# ultra-violet-tooth-sensor-mk-2_3.net
KiCad netlist of a schematic drawn in EAGLE
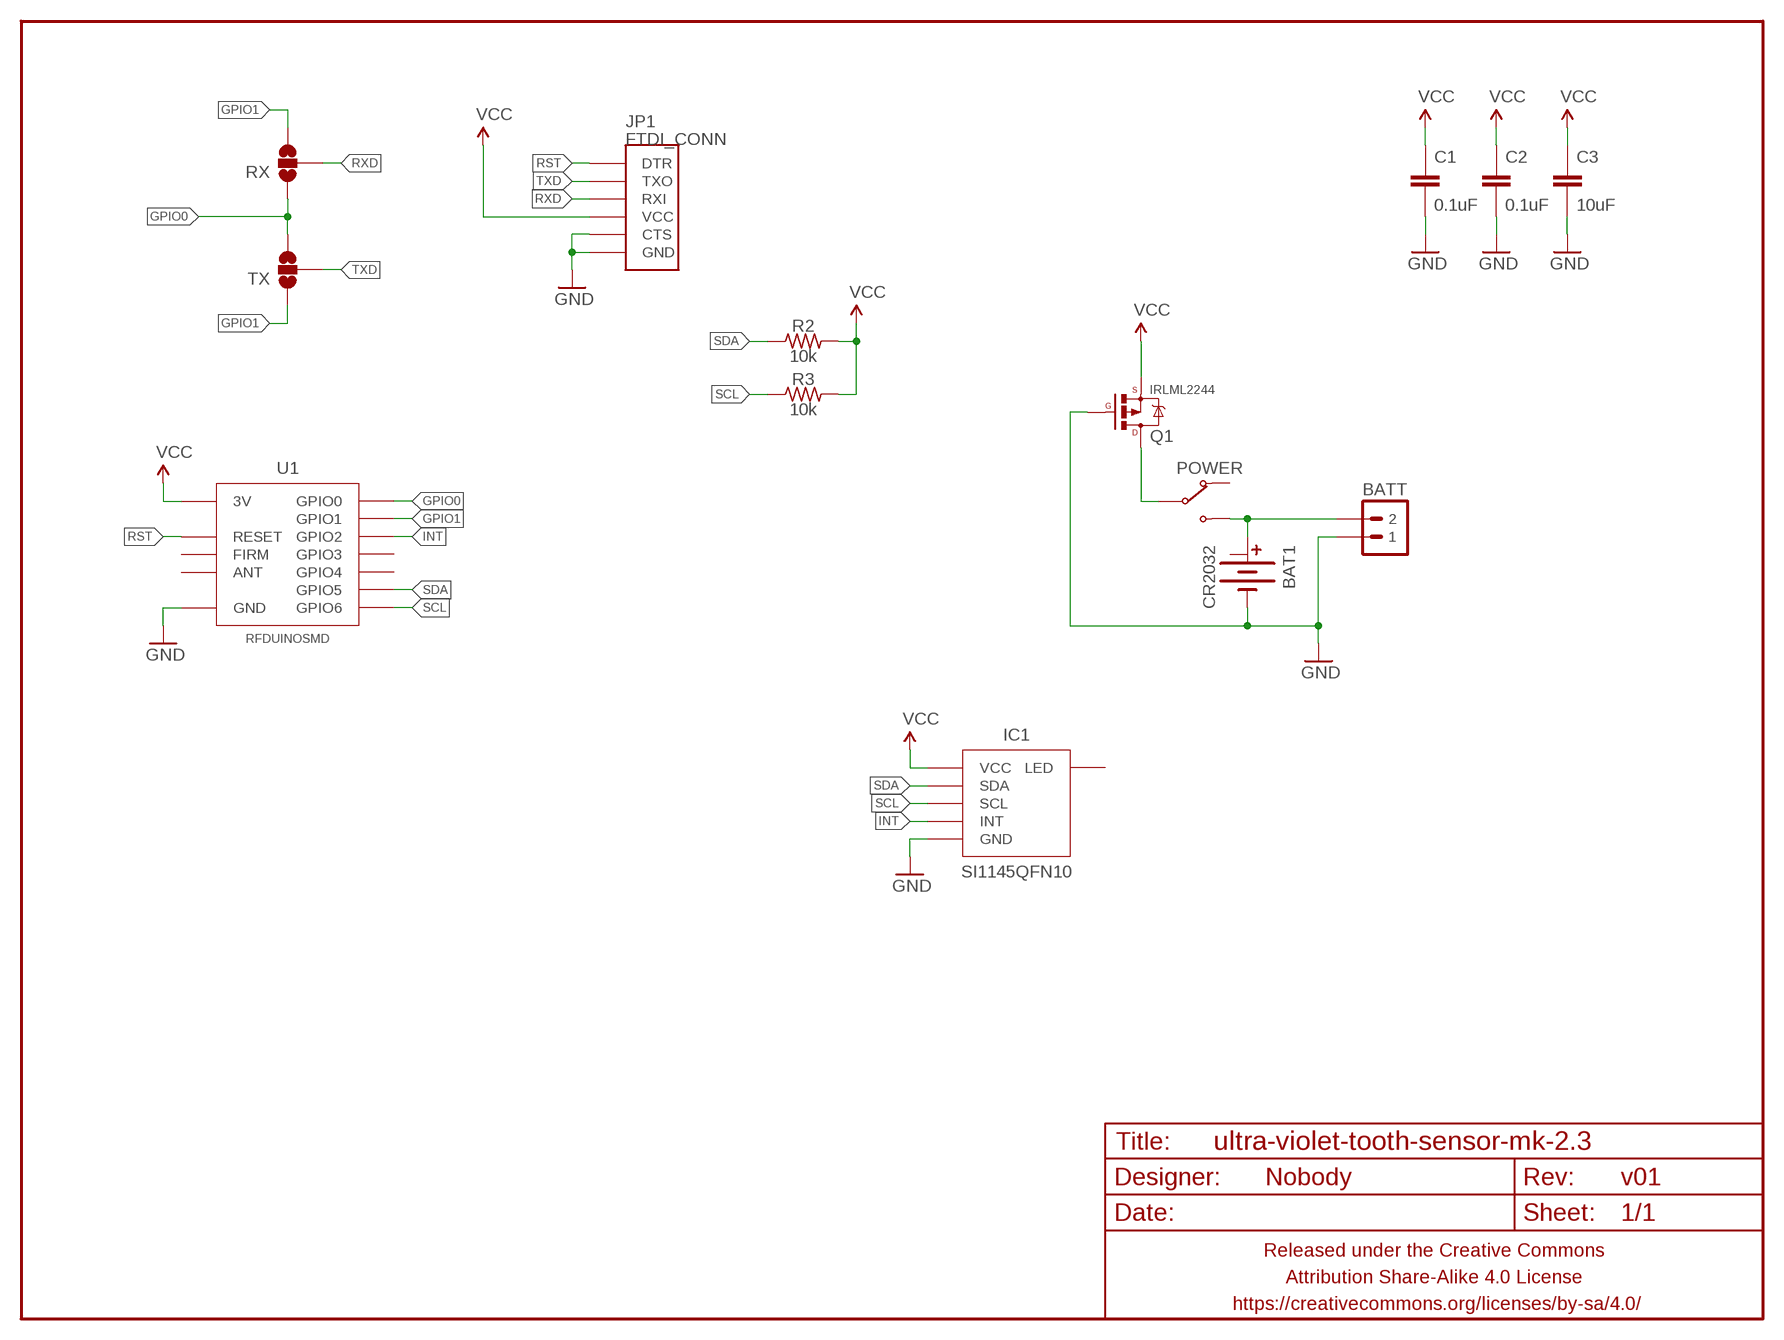
[diagram p0: schematic, sheet 1]

(export (version "E")
  (design (tool "Eeschema 10.0.6"))
  (components
    (comp (ref "BAT1")
      (value "CR2032")
      (footprint "eagle-import:BATTCON_20MM_MINE_STAHPIT")
      (libsource (lib "eagle-import") (part "BATTERY-COINCR2032_SMD_TIGHT"))
    )
    (comp (ref "BATT")
      (value "M02PTH-CENTERED-R+")
      (footprint "eagle-import:1X02-CENTER-R+")
      (libsource (lib "eagle-import") (part "M02PTH-CENTERED-R+"))
    )
    (comp (ref "C1")
      (value "0.1uF")
      (footprint "eagle-import:C0805")
      (libsource (lib "eagle-import") (part "CAPACITOR-CERAMICC0805"))
    )
    (comp (ref "C2")
      (value "0.1uF")
      (footprint "eagle-import:C0603")
      (libsource (lib "eagle-import") (part "CAPACITOR-CERAMICC0603"))
    )
    (comp (ref "C3")
      (value "10uF")
      (footprint "eagle-import:C1206")
      (libsource (lib "eagle-import") (part "CAPACITOR-CERAMICC1206"))
    )
    (comp (ref "FRAME1")
      (value "FRAME-LETTERNO_PACKAGE")
      (footprint "eagle-import:DUMMY")
      (fields (field (name "DESIGNER") "Nobody"))
      (libsource (lib "eagle-import") (part "FRAME-LETTERNO_PACKAGE"))
    )
    (comp (ref "IC1")
      (value "SI1145QFN10")
      (footprint "eagle-import:SI1145")
      (libsource (lib "eagle-import") (part "SI1145QFN10"))
    )
    (comp (ref "JP1")
      (value "FTDI_CONN")
      (footprint "eagle-import:FTDI_CONN")
      (libsource (lib "eagle-import") (part "FTDI_CONN"))
    )
    (comp (ref "POWER")
      (value "SWITCH-SPDTPCM12SMTR")
      (footprint "eagle-import:SWITCH-SPDT-SMD-RA-PCM12SMTR")
      (libsource (lib "eagle-import") (part "SWITCH-SPDTPCM12SMTR"))
    )
    (comp (ref "Q1")
      (value "IRLML2244")
      (footprint "eagle-import:SOT23-3")
      (libsource (lib "eagle-import") (part "MOSFET-PCHANNELIRLML2244"))
    )
    (comp (ref "R2")
      (value "10k")
      (footprint "eagle-import:R0603")
      (libsource (lib "eagle-import") (part "RESISTORR0603"))
    )
    (comp (ref "R3")
      (value "10k")
      (footprint "eagle-import:R0603")
      (libsource (lib "eagle-import") (part "RESISTORR0603"))
    )
    (comp (ref "RX")
      (value "JUMPER-PAD-3-NOFULL_BOX_SILK")
      (footprint "eagle-import:PAD-JUMPER-3-NO_YES_SILK_FULL_BOX")
      (libsource (lib "eagle-import") (part "JUMPER-PAD-3-NOFULL_BOX_SILK"))
    )
    (comp (ref "TX")
      (value "JUMPER-PAD-3-NOFULL_BOX_SILK")
      (footprint "eagle-import:PAD-JUMPER-3-NO_YES_SILK_FULL_BOX")
      (libsource (lib "eagle-import") (part "JUMPER-PAD-3-NOFULL_BOX_SILK"))
    )
    (comp (ref "U1")
      (value "RFDUINOSMD")
      (footprint "eagle-import:RFDUINO-SMD")
      (libsource (lib "eagle-import") (part "RFDUINOSMD"))
    )
  )
  (nets
    (net (code "1") (name "GND") (class "Default")
      (node (ref "BAT1") (pin "BOTTOM") (pinfunction "-_BOTTOM") (pintype "bidirectional"))
      (node (ref "BATT") (pin "1") (pinfunction "1_1") (pintype "passive"))
      (node (ref "C1") (pin "2") (pinfunction "2_2") (pintype "passive"))
      (node (ref "C2") (pin "2") (pinfunction "2_2") (pintype "passive"))
      (node (ref "C3") (pin "2") (pinfunction "2_2") (pintype "passive"))
      (node (ref "IC1") (pin "GND") (pinfunction "GND_GND") (pintype "bidirectional"))
      (node (ref "JP1") (pin "CTS") (pinfunction "CTS_CTS") (pintype "bidirectional"))
      (node (ref "JP1") (pin "GND") (pinfunction "GND_GND") (pintype "bidirectional"))
      (node (ref "Q1") (pin "1") (pinfunction "G_1") (pintype "passive"))
      (node (ref "U1") (pin "GND@1") (pinfunction "GND_GND@1") (pintype "bidirectional"))
      (node (ref "U1") (pin "GND@2") (pinfunction "GND_GND@2") (pintype "bidirectional"))
      (node (ref "U1") (pin "GND@3") (pinfunction "GND_GND@3") (pintype "bidirectional"))
      (node (ref "U1") (pin "GND@4") (pinfunction "GND_GND@4") (pintype "bidirectional"))
      (node (ref "U1") (pin "GND@5") (pinfunction "GND_GND@5") (pintype "bidirectional"))
      (node (ref "U1") (pin "GND@6") (pinfunction "GND_GND@6") (pintype "bidirectional"))
      (node (ref "U1") (pin "GND@7") (pinfunction "GND_GND@7") (pintype "bidirectional"))
      (node (ref "U1") (pin "GND@8") (pinfunction "GND_GND@8") (pintype "bidirectional"))
    )
    (net (code "2") (name "GPIO0") (class "Default")
      (node (ref "RX") (pin "1") (pinfunction "1_1") (pintype "passive"))
      (node (ref "TX") (pin "3") (pinfunction "3_3") (pintype "passive"))
      (node (ref "U1") (pin "GPIO0") (pinfunction "GPIO0_GPIO0") (pintype "bidirectional"))
    )
    (net (code "3") (name "GPIO1") (class "Default")
      (node (ref "RX") (pin "3") (pinfunction "3_3") (pintype "passive"))
      (node (ref "TX") (pin "1") (pinfunction "1_1") (pintype "passive"))
      (node (ref "U1") (pin "GPIO1") (pinfunction "GPIO1_GPIO1") (pintype "bidirectional"))
    )
    (net (code "4") (name "INT") (class "Default")
      (node (ref "IC1") (pin "INT") (pinfunction "INT_INT") (pintype "bidirectional"))
      (node (ref "U1") (pin "GPIO2") (pinfunction "GPIO2_GPIO2") (pintype "bidirectional"))
    )
    (net (code "5") (name "Net-(BAT1-+)") (class "Default")
      (node (ref "BAT1") (pin "TOP@1") (pinfunction "+_TOP@1") (pintype "bidirectional"))
      (node (ref "BATT") (pin "2") (pinfunction "2_2") (pintype "passive"))
      (node (ref "POWER") (pin "3") (pinfunction "NO_3") (pintype "passive"))
    )
    (net (code "6") (name "Net-(POWER-COM)") (class "Default")
      (node (ref "POWER") (pin "2") (pinfunction "COM_2") (pintype "passive"))
      (node (ref "Q1") (pin "3") (pinfunction "D_3") (pintype "passive"))
    )
    (net (code "7") (name "RST") (class "Default")
      (node (ref "JP1") (pin "DTR") (pinfunction "DTR_DTR") (pintype "bidirectional"))
      (node (ref "U1") (pin "RESET") (pinfunction "RESET_RESET") (pintype "bidirectional"))
    )
    (net (code "8") (name "RXD") (class "Default")
      (node (ref "JP1") (pin "RXI") (pinfunction "RXI_RXI") (pintype "bidirectional"))
      (node (ref "RX") (pin "2") (pinfunction "2_2") (pintype "passive"))
    )
    (net (code "9") (name "SCL") (class "Default")
      (node (ref "IC1") (pin "SCL") (pinfunction "SCL_SCL") (pintype "bidirectional"))
      (node (ref "R3") (pin "1") (pinfunction "1_1") (pintype "passive"))
      (node (ref "U1") (pin "GPIO6") (pinfunction "GPIO6_GPIO6") (pintype "bidirectional"))
    )
    (net (code "10") (name "SDA") (class "Default")
      (node (ref "IC1") (pin "SDA") (pinfunction "SDA_SDA") (pintype "bidirectional"))
      (node (ref "R2") (pin "1") (pinfunction "1_1") (pintype "passive"))
      (node (ref "U1") (pin "GPIO5") (pinfunction "GPIO5_GPIO5") (pintype "bidirectional"))
    )
    (net (code "11") (name "TXD") (class "Default")
      (node (ref "JP1") (pin "TXO") (pinfunction "TXO_TXO") (pintype "bidirectional"))
      (node (ref "TX") (pin "2") (pinfunction "2_2") (pintype "passive"))
    )
    (net (code "12") (name "VCC") (class "Default")
      (node (ref "C1") (pin "1") (pinfunction "1_1") (pintype "passive"))
      (node (ref "C2") (pin "1") (pinfunction "1_1") (pintype "passive"))
      (node (ref "C3") (pin "1") (pinfunction "1_1") (pintype "passive"))
      (node (ref "IC1") (pin "VCC@1") (pinfunction "VCC_VCC@1") (pintype "bidirectional"))
      (node (ref "IC1") (pin "VCC@2") (pinfunction "VCC_VCC@2") (pintype "bidirectional"))
      (node (ref "IC1") (pin "VCC@3") (pinfunction "VCC_VCC@3") (pintype "bidirectional"))
      (node (ref "JP1") (pin "VCC") (pinfunction "VCC_VCC") (pintype "bidirectional"))
      (node (ref "Q1") (pin "2") (pinfunction "S_2") (pintype "passive"))
      (node (ref "R2") (pin "2") (pinfunction "2_2") (pintype "passive"))
      (node (ref "R3") (pin "2") (pinfunction "2_2") (pintype "passive"))
      (node (ref "U1") (pin "3V") (pinfunction "3V_3V") (pintype "bidirectional"))
    )
    (net (code "13") (name "unconnected-(BAT1-+1-PadTOP@2)") (class "Default")
      (node (ref "BAT1") (pin "TOP@2") (pinfunction "+1_TOP@2") (pintype "bidirectional"))
    )
    (net (code "14") (name "unconnected-(IC1-PadLED)") (class "Default")
      (node (ref "IC1") (pin "LED") (pinfunction "LED_LED") (pintype "bidirectional"))
    )
    (net (code "15") (name "unconnected-(POWER-NC-Pad1)") (class "Default")
      (node (ref "POWER") (pin "1") (pinfunction "NC_1") (pintype "passive"))
    )
    (net (code "16") (name "unconnected-(U1-FIRM-PadFACTORY)") (class "Default")
      (node (ref "U1") (pin "FACTORY") (pinfunction "FIRM_FACTORY") (pintype "bidirectional"))
    )
    (net (code "17") (name "unconnected-(U1-PadANT)") (class "Default")
      (node (ref "U1") (pin "ANT") (pinfunction "ANT_ANT") (pintype "bidirectional"))
    )
    (net (code "18") (name "unconnected-(U1-PadGPIO3)") (class "Default")
      (node (ref "U1") (pin "GPIO3") (pinfunction "GPIO3_GPIO3") (pintype "bidirectional"))
    )
    (net (code "19") (name "unconnected-(U1-PadGPIO4)") (class "Default")
      (node (ref "U1") (pin "GPIO4") (pinfunction "GPIO4_GPIO4") (pintype "bidirectional"))
    )
  )
)
